# rpi_industrial_hat.net
KiCad netlist of a schematic drawn in EAGLE
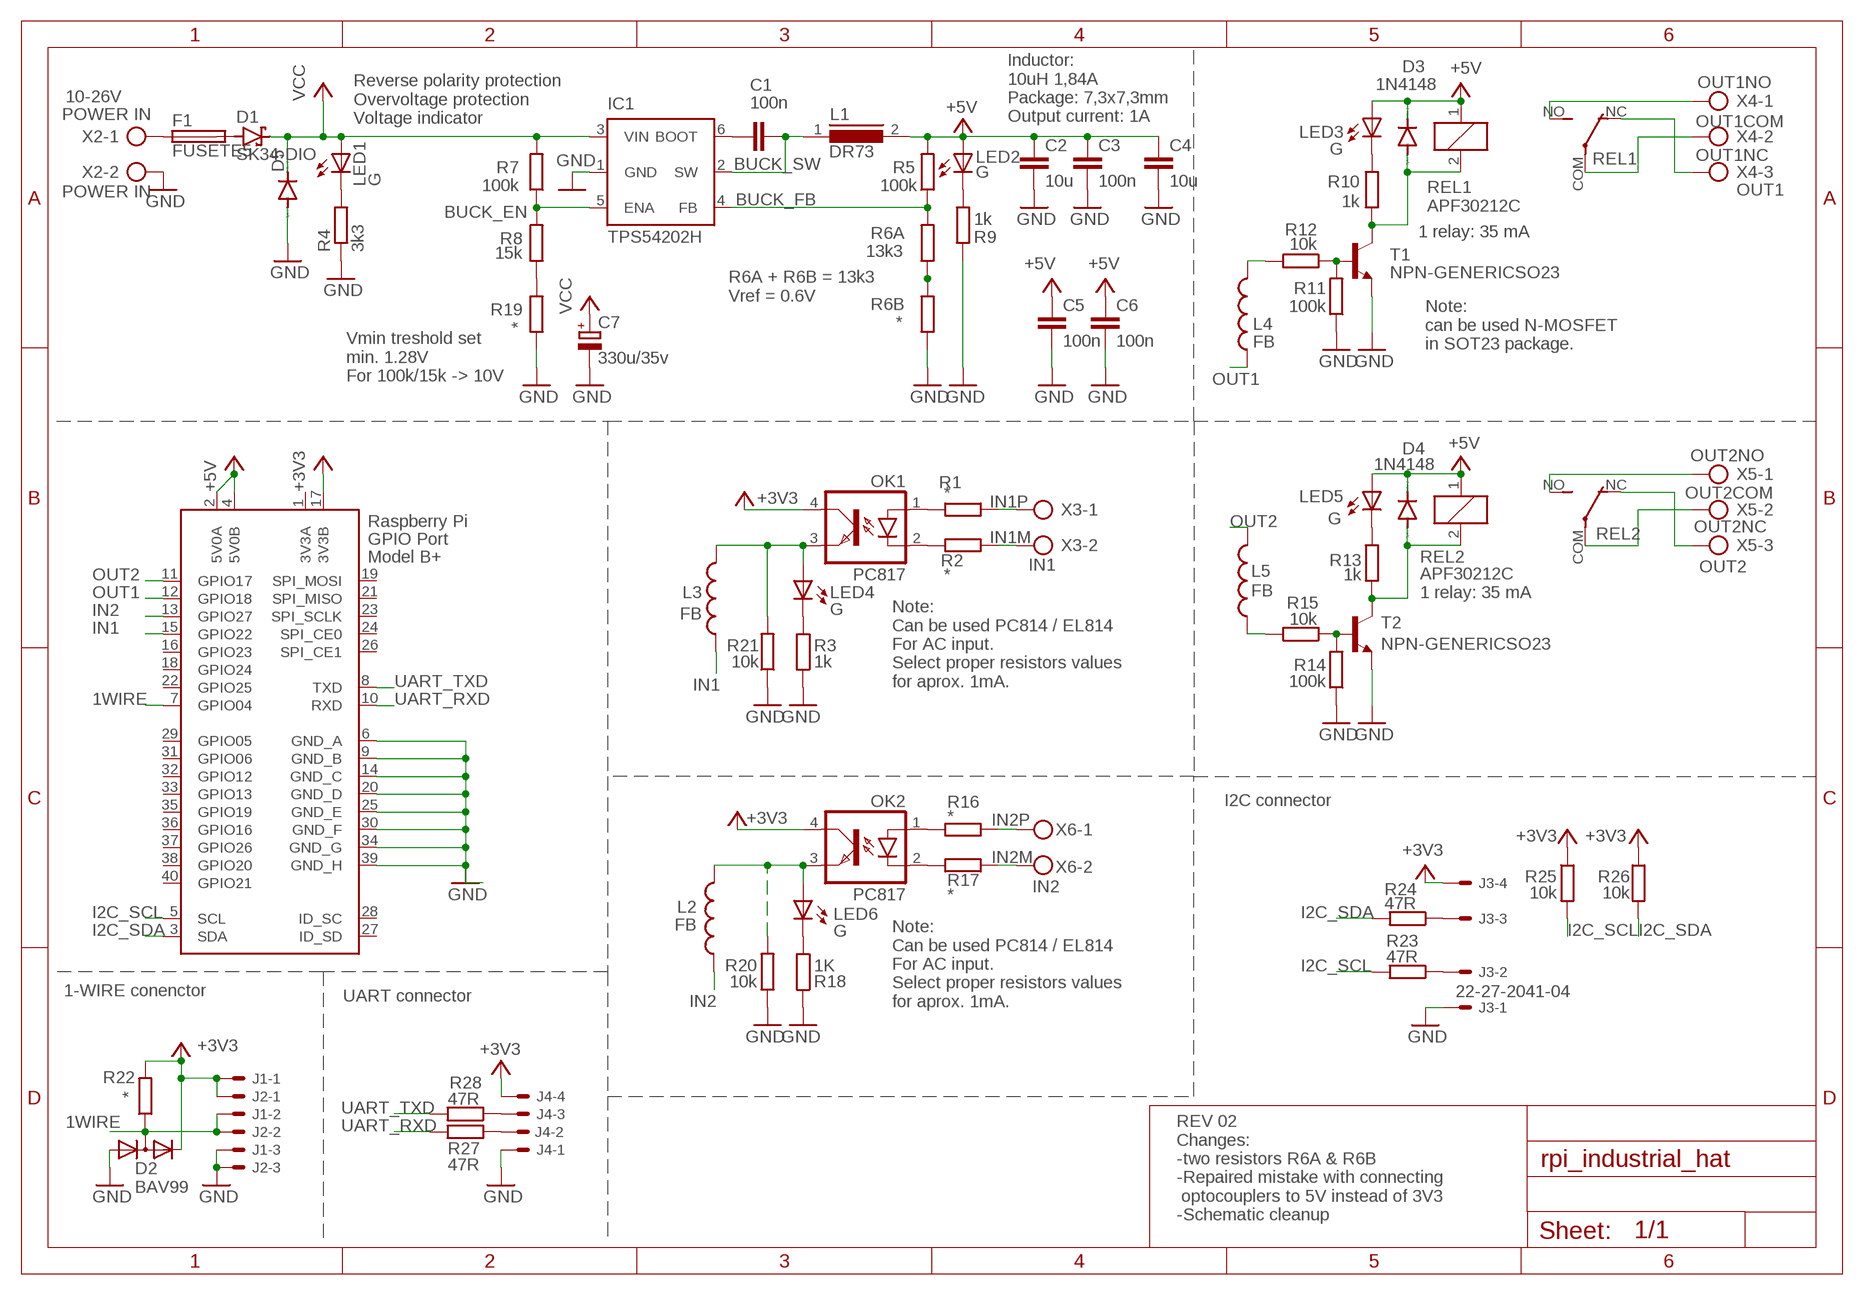
[diagram p0: schematic, sheet 1]

(export (version "E")
  (design (tool "Eeschema 10.0.6"))
  (components
    (comp (ref "C1")
      (value "100n")
      (footprint "eagle-import:C0603")
      (libsource (lib "eagle-import") (part "C-EUC0603"))
    )
    (comp (ref "C2")
      (value "10u")
      (footprint "eagle-import:C0805")
      (libsource (lib "eagle-import") (part "C-EUC0805"))
    )
    (comp (ref "C3")
      (value "100n")
      (footprint "eagle-import:C0603")
      (libsource (lib "eagle-import") (part "C-EUC0603"))
    )
    (comp (ref "C4")
      (value "10u")
      (footprint "eagle-import:C0805")
      (libsource (lib "eagle-import") (part "C-EUC0805"))
    )
    (comp (ref "C5")
      (value "100n")
      (footprint "eagle-import:C0603")
      (libsource (lib "eagle-import") (part "C-EUC0603"))
    )
    (comp (ref "C6")
      (value "100n")
      (footprint "eagle-import:C0603")
      (libsource (lib "eagle-import") (part "C-EUC0603"))
    )
    (comp (ref "C7")
      (value "330u/35v")
      (footprint "eagle-import:E5-10,5")
      (libsource (lib "eagle-import") (part "CPOL-EUE5-10.5"))
    )
    (comp (ref "D1")
      (value "SK34-DIO")
      (footprint "eagle-import:SMC")
      (libsource (lib "eagle-import") (part "SCHOTTKY-DIODESMC"))
    )
    (comp (ref "D2")
      (value "BAV99")
      (footprint "eagle-import:SOT23")
      (libsource (lib "eagle-import") (part "BAV99"))
    )
    (comp (ref "D3")
      (value "1N4148")
      (footprint "eagle-import:MINIMELF")
      (libsource (lib "eagle-import") (part "DIODE-MINIMELF"))
    )
    (comp (ref "D4")
      (value "1N4148")
      (footprint "eagle-import:MINIMELF")
      (libsource (lib "eagle-import") (part "DIODE-MINIMELF"))
    )
    (comp (ref "D5")
      (value "DIODE-DO214AA")
      (footprint "eagle-import:DO214AA")
      (libsource (lib "eagle-import") (part "DIODE-DO214AA"))
    )
    (comp (ref "F1")
      (value "FUSETE5")
      (footprint "eagle-import:TE5")
      (libsource (lib "eagle-import") (part "FUSETE5"))
    )
    (comp (ref "IC1")
      (value "TPS54202H")
      (footprint "eagle-import:SOT23-6")
      (libsource (lib "eagle-import") (part "TPS54202H"))
    )
    (comp (ref "J1")
      (value "22-27-2031-03")
      (footprint "eagle-import:6410-03")
      (fields (field (name "MF") "MOLEX"))
      (libsource (lib "eagle-import") (part "22-?-0327-2031"))
    )
    (comp (ref "J2")
      (value "22-27-2031-03")
      (footprint "eagle-import:6410-03")
      (fields (field (name "MF") "MOLEX"))
      (libsource (lib "eagle-import") (part "22-?-0327-2031"))
    )
    (comp (ref "J3")
      (value "22-27-2041-04")
      (footprint "eagle-import:6410-04")
      (fields (field (name "MF") "MOLEX"))
      (libsource (lib "eagle-import") (part "22-?-0427-2041"))
    )
    (comp (ref "J4")
      (value "22-27-2041-04")
      (footprint "eagle-import:6410-04")
      (fields (field (name "MF") "MOLEX"))
      (libsource (lib "eagle-import") (part "22-?-0427-2041"))
    )
    (comp (ref "L1")
      (value "DR73")
      (footprint "eagle-import:DR73")
      (libsource (lib "eagle-import") (part "DR73"))
    )
    (comp (ref "L2")
      (value "FB")
      (footprint "eagle-import:0603")
      (libsource (lib "eagle-import") (part "INDUCTOR0603"))
    )
    (comp (ref "L3")
      (value "FB")
      (footprint "eagle-import:0603")
      (libsource (lib "eagle-import") (part "INDUCTOR0603"))
    )
    (comp (ref "L4")
      (value "FB")
      (footprint "eagle-import:0603")
      (libsource (lib "eagle-import") (part "INDUCTOR0603"))
    )
    (comp (ref "L5")
      (value "FB")
      (footprint "eagle-import:0603")
      (libsource (lib "eagle-import") (part "INDUCTOR0603"))
    )
    (comp (ref "LED1")
      (value "G")
      (footprint "eagle-import:CHIP-LED0603")
      (libsource (lib "eagle-import") (part "LEDCHIP-LED0603"))
    )
    (comp (ref "LED2")
      (value "G")
      (footprint "eagle-import:CHIP-LED0603")
      (libsource (lib "eagle-import") (part "LEDCHIP-LED0603"))
    )
    (comp (ref "LED3")
      (value "G")
      (footprint "eagle-import:CHIP-LED0603")
      (libsource (lib "eagle-import") (part "LEDCHIP-LED0603"))
    )
    (comp (ref "LED4")
      (value "G")
      (footprint "eagle-import:CHIP-LED0603")
      (libsource (lib "eagle-import") (part "LEDCHIP-LED0603"))
    )
    (comp (ref "LED5")
      (value "G")
      (footprint "eagle-import:CHIP-LED0603")
      (libsource (lib "eagle-import") (part "LEDCHIP-LED0603"))
    )
    (comp (ref "LED6")
      (value "G")
      (footprint "eagle-import:CHIP-LED0603")
      (libsource (lib "eagle-import") (part "LEDCHIP-LED0603"))
    )
    (comp (ref "OK1")
      (value "PC817")
      (footprint "eagle-import:DIL04")
      (fields (field (name "MPN") "PC817X4J000F"))
      (libsource (lib "eagle-import") (part "PC817"))
    )
    (comp (ref "OK2")
      (value "PC817")
      (footprint "eagle-import:DIL04")
      (fields (field (name "MPN") "PC817X4J000F"))
      (libsource (lib "eagle-import") (part "PC817"))
    )
    (comp (ref "R1")
      (value "*")
      (footprint "eagle-import:0204_7_SMD")
      (libsource (lib "eagle-import") (part "R_PROTO_0204/7_0805"))
    )
    (comp (ref "R2")
      (value "*")
      (footprint "eagle-import:0204_7_SMD")
      (libsource (lib "eagle-import") (part "R_PROTO_0204/7_0805"))
    )
    (comp (ref "R3")
      (value "1k")
      (footprint "eagle-import:R0603")
      (libsource (lib "eagle-import") (part "R-EU_R0603"))
    )
    (comp (ref "R4")
      (value "3k3")
      (footprint "eagle-import:R0603")
      (libsource (lib "eagle-import") (part "R-EU_R0603"))
    )
    (comp (ref "R5")
      (value "100k")
      (footprint "eagle-import:R0603")
      (libsource (lib "eagle-import") (part "R-EU_R0603"))
    )
    (comp (ref "R6A")
      (value "13k3")
      (footprint "eagle-import:R0603")
      (libsource (lib "eagle-import") (part "R-EU_R0603"))
    )
    (comp (ref "R6B")
      (value "*")
      (footprint "eagle-import:R0603")
      (libsource (lib "eagle-import") (part "R-EU_R0603"))
    )
    (comp (ref "R7")
      (value "100k")
      (footprint "eagle-import:R0603")
      (libsource (lib "eagle-import") (part "R-EU_R0603"))
    )
    (comp (ref "R8")
      (value "15k")
      (footprint "eagle-import:R0603")
      (libsource (lib "eagle-import") (part "R-EU_R0603"))
    )
    (comp (ref "R9")
      (value "1k")
      (footprint "eagle-import:R0603")
      (libsource (lib "eagle-import") (part "R-EU_R0603"))
    )
    (comp (ref "R10")
      (value "1k")
      (footprint "eagle-import:R0603")
      (libsource (lib "eagle-import") (part "R-EU_R0603"))
    )
    (comp (ref "R11")
      (value "100k")
      (footprint "eagle-import:R0603")
      (libsource (lib "eagle-import") (part "R-EU_R0603"))
    )
    (comp (ref "R12")
      (value "10k")
      (footprint "eagle-import:R0603")
      (libsource (lib "eagle-import") (part "R-EU_R0603"))
    )
    (comp (ref "R13")
      (value "1k")
      (footprint "eagle-import:R0603")
      (libsource (lib "eagle-import") (part "R-EU_R0603"))
    )
    (comp (ref "R14")
      (value "100k")
      (footprint "eagle-import:R0603")
      (libsource (lib "eagle-import") (part "R-EU_R0603"))
    )
    (comp (ref "R15")
      (value "10k")
      (footprint "eagle-import:R0603")
      (libsource (lib "eagle-import") (part "R-EU_R0603"))
    )
    (comp (ref "R16")
      (value "*")
      (footprint "eagle-import:0204_7_SMD")
      (libsource (lib "eagle-import") (part "R_PROTO_0204/7_0805"))
    )
    (comp (ref "R17")
      (value "*")
      (footprint "eagle-import:0204_7_SMD")
      (libsource (lib "eagle-import") (part "R_PROTO_0204/7_0805"))
    )
    (comp (ref "R18")
      (value "1K")
      (footprint "eagle-import:R0603")
      (libsource (lib "eagle-import") (part "R-EU_R0603"))
    )
    (comp (ref "R19")
      (value "*")
      (footprint "eagle-import:R0603")
      (libsource (lib "eagle-import") (part "R-EU_R0603"))
    )
    (comp (ref "R20")
      (value "10k")
      (footprint "eagle-import:R0603")
      (libsource (lib "eagle-import") (part "R-EU_R0603"))
    )
    (comp (ref "R21")
      (value "10k")
      (footprint "eagle-import:R0603")
      (libsource (lib "eagle-import") (part "R-EU_R0603"))
    )
    (comp (ref "R22")
      (value "*")
      (footprint "eagle-import:R0603")
      (libsource (lib "eagle-import") (part "R-EU_R0603"))
    )
    (comp (ref "R23")
      (value "47R")
      (footprint "eagle-import:R0603")
      (libsource (lib "eagle-import") (part "R-EU_R0603"))
    )
    (comp (ref "R24")
      (value "47R")
      (footprint "eagle-import:R0603")
      (libsource (lib "eagle-import") (part "R-EU_R0603"))
    )
    (comp (ref "R25")
      (value "10k")
      (footprint "eagle-import:R0603")
      (libsource (lib "eagle-import") (part "R-EU_R0603"))
    )
    (comp (ref "R26")
      (value "10k")
      (footprint "eagle-import:R0603")
      (libsource (lib "eagle-import") (part "R-EU_R0603"))
    )
    (comp (ref "R27")
      (value "47R")
      (footprint "eagle-import:R0603")
      (libsource (lib "eagle-import") (part "R-EU_R0603"))
    )
    (comp (ref "R28")
      (value "47R")
      (footprint "eagle-import:R0603")
      (libsource (lib "eagle-import") (part "R-EU_R0603"))
    )
    (comp (ref "REL1")
      (value "APF30212C")
      (footprint "eagle-import:APF30212C")
      (libsource (lib "eagle-import") (part "APF30212C"))
    )
    (comp (ref "REL2")
      (value "APF30212C")
      (footprint "eagle-import:APF30212C")
      (libsource (lib "eagle-import") (part "APF30212C"))
    )
    (comp (ref "T1")
      (value "NPN-GENERICSO23")
      (footprint "eagle-import:SOT23")
      (libsource (lib "eagle-import") (part "NPN-GENERICSO23"))
    )
    (comp (ref "T2")
      (value "NPN-GENERICSO23")
      (footprint "eagle-import:SOT23")
      (libsource (lib "eagle-import") (part "NPN-GENERICSO23"))
    )
    (comp (ref "X1")
      (value "RASPI_BOARD_B+#_E4P")
      (footprint "eagle-import:RASPI_BOARD_B+_EDGES_4DRILL_PAD")
      (libsource (lib "eagle-import") (part "RASPI_BOARD_B+#_E4P"))
    )
    (comp (ref "X2")
      (value "POWER IN")
      (footprint "eagle-import:AK500_2")
      (libsource (lib "eagle-import") (part "AK500/2"))
    )
    (comp (ref "X3")
      (value "IN1")
      (footprint "eagle-import:AK500_2")
      (libsource (lib "eagle-import") (part "AK500/2"))
    )
    (comp (ref "X4")
      (value "OUT1")
      (footprint "eagle-import:AK500_3")
      (libsource (lib "eagle-import") (part "AK500/3"))
    )
    (comp (ref "X5")
      (value "OUT2")
      (footprint "eagle-import:AK500_3")
      (libsource (lib "eagle-import") (part "AK500/3"))
    )
    (comp (ref "X6")
      (value "IN2")
      (footprint "eagle-import:AK500_2")
      (libsource (lib "eagle-import") (part "AK500/2"))
    )
  )
  (nets
    (net (code "1") (name "+3V3") (class "Default")
      (node (ref "D2") (pin "2") (pinfunction "K2_2") (pintype "passive"))
      (node (ref "J1") (pin "1") (pinfunction "S_1") (pintype "passive"))
      (node (ref "J2") (pin "1") (pinfunction "S_1") (pintype "passive"))
      (node (ref "J3") (pin "4") (pinfunction "S_4") (pintype "passive"))
      (node (ref "J4") (pin "4") (pinfunction "S_4") (pintype "passive"))
      (node (ref "OK1") (pin "4") (pinfunction "COL_4") (pintype "passive"))
      (node (ref "OK2") (pin "4") (pinfunction "COL_4") (pintype "passive"))
      (node (ref "R22") (pin "2") (pinfunction "2_2") (pintype "passive"))
      (node (ref "R25") (pin "1") (pinfunction "1_1") (pintype "passive"))
      (node (ref "R26") (pin "1") (pinfunction "1_1") (pintype "passive"))
      (node (ref "X1") (pin "17") (pinfunction "3V3B_17") (pintype "power_in"))
    )
    (net (code "2") (name "+5V") (class "Default")
      (node (ref "C2") (pin "1") (pinfunction "1_1") (pintype "passive"))
      (node (ref "C3") (pin "1") (pinfunction "1_1") (pintype "passive"))
      (node (ref "C4") (pin "1") (pinfunction "1_1") (pintype "passive"))
      (node (ref "C5") (pin "1") (pinfunction "1_1") (pintype "passive"))
      (node (ref "C6") (pin "1") (pinfunction "1_1") (pintype "passive"))
      (node (ref "D3") (pin "C") (pinfunction "C_C") (pintype "passive"))
      (node (ref "D4") (pin "C") (pinfunction "C_C") (pintype "passive"))
      (node (ref "L1") (pin "2") (pinfunction "2_2") (pintype "passive"))
      (node (ref "LED2") (pin "A") (pinfunction "A_A") (pintype "passive"))
      (node (ref "LED3") (pin "A") (pinfunction "A_A") (pintype "passive"))
      (node (ref "LED5") (pin "A") (pinfunction "A_A") (pintype "passive"))
      (node (ref "R5") (pin "2") (pinfunction "2_2") (pintype "passive"))
      (node (ref "REL1") (pin "1") (pinfunction "1_1") (pintype "passive"))
      (node (ref "REL2") (pin "1") (pinfunction "1_1") (pintype "passive"))
      (node (ref "X1") (pin "2") (pinfunction "5V0A_2") (pintype "power_in"))
      (node (ref "X1") (pin "4") (pinfunction "5V0B_4") (pintype "power_in"))
    )
    (net (code "3") (name "/1WIRE") (class "Default")
      (node (ref "D2") (pin "3") (pinfunction "K1A2_3") (pintype "passive"))
      (node (ref "J1") (pin "2") (pinfunction "S_2") (pintype "passive"))
      (node (ref "J2") (pin "2") (pinfunction "S_2") (pintype "passive"))
      (node (ref "R22") (pin "1") (pinfunction "1_1") (pintype "passive"))
      (node (ref "X1") (pin "7") (pinfunction "GPIO04_7") (pintype "bidirectional"))
    )
    (net (code "4") (name "/3V3A") (class "Default")
      (node (ref "X1") (pin "1") (pinfunction "3V3A_1") (pintype "power_in"))
    )
    (net (code "5") (name "/BUCK_EN") (class "Default")
      (node (ref "IC1") (pin "5") (pinfunction "ENA_5") (pintype "input"))
      (node (ref "R7") (pin "1") (pinfunction "1_1") (pintype "passive"))
      (node (ref "R8") (pin "2") (pinfunction "2_2") (pintype "passive"))
    )
    (net (code "6") (name "/BUCK_FB") (class "Default")
      (node (ref "IC1") (pin "4") (pinfunction "FB_4") (pintype "input"))
      (node (ref "R5") (pin "1") (pinfunction "1_1") (pintype "passive"))
      (node (ref "R6A") (pin "2") (pinfunction "2_2") (pintype "passive"))
    )
    (net (code "7") (name "/BUCK_SW") (class "Default")
      (node (ref "C1") (pin "2") (pinfunction "2_2") (pintype "passive"))
      (node (ref "IC1") (pin "2") (pinfunction "SW_2") (pintype "output"))
      (node (ref "L1") (pin "1") (pinfunction "1_1") (pintype "passive"))
    )
    (net (code "8") (name "/I2C_SCL") (class "Default")
      (node (ref "R23") (pin "2") (pinfunction "2_2") (pintype "passive"))
      (node (ref "R25") (pin "2") (pinfunction "2_2") (pintype "passive"))
      (node (ref "X1") (pin "5") (pinfunction "SCL_5") (pintype "bidirectional"))
    )
    (net (code "9") (name "/I2C_SDA") (class "Default")
      (node (ref "R24") (pin "2") (pinfunction "2_2") (pintype "passive"))
      (node (ref "R26") (pin "2") (pinfunction "2_2") (pintype "passive"))
      (node (ref "X1") (pin "3") (pinfunction "SDA_3") (pintype "bidirectional"))
    )
    (net (code "10") (name "/IN1") (class "Default")
      (node (ref "L3") (pin "1") (pinfunction "1_1") (pintype "passive"))
      (node (ref "X1") (pin "15") (pinfunction "GPIO22_15") (pintype "bidirectional"))
    )
    (net (code "11") (name "/IN1M") (class "Default")
      (node (ref "R2") (pin "1") (pinfunction "1_1") (pintype "passive"))
      (node (ref "X3") (pin "2") (pinfunction "KL_2") (pintype "passive"))
    )
    (net (code "12") (name "/IN1P") (class "Default")
      (node (ref "R1") (pin "1") (pinfunction "1_1") (pintype "passive"))
      (node (ref "X3") (pin "1") (pinfunction "KL_1") (pintype "passive"))
    )
    (net (code "13") (name "/IN2") (class "Default")
      (node (ref "L2") (pin "1") (pinfunction "1_1") (pintype "passive"))
      (node (ref "X1") (pin "13") (pinfunction "GPIO27_13") (pintype "bidirectional"))
    )
    (net (code "14") (name "/IN2M") (class "Default")
      (node (ref "R17") (pin "1") (pinfunction "1_1") (pintype "passive"))
      (node (ref "X6") (pin "2") (pinfunction "KL_2") (pintype "passive"))
    )
    (net (code "15") (name "/IN2P") (class "Default")
      (node (ref "R16") (pin "1") (pinfunction "1_1") (pintype "passive"))
      (node (ref "X6") (pin "1") (pinfunction "KL_1") (pintype "passive"))
    )
    (net (code "16") (name "/OUT1") (class "Default")
      (node (ref "L4") (pin "1") (pinfunction "1_1") (pintype "passive"))
      (node (ref "X1") (pin "12") (pinfunction "GPIO18_12") (pintype "bidirectional"))
    )
    (net (code "17") (name "/OUT1COM") (class "Default")
      (node (ref "REL1") (pin "COM") (pinfunction "P_COM") (pintype "passive"))
      (node (ref "X4") (pin "2") (pinfunction "KL_2") (pintype "passive"))
    )
    (net (code "18") (name "/OUT1NC") (class "Default")
      (node (ref "REL1") (pin "NC") (pinfunction "O_NC") (pintype "passive"))
      (node (ref "X4") (pin "3") (pinfunction "KL_3") (pintype "passive"))
    )
    (net (code "19") (name "/OUT1NO") (class "Default")
      (node (ref "REL1") (pin "NO") (pinfunction "S_NO") (pintype "passive"))
      (node (ref "X4") (pin "1") (pinfunction "KL_1") (pintype "passive"))
    )
    (net (code "20") (name "/OUT2") (class "Default")
      (node (ref "L5") (pin "2") (pinfunction "2_2") (pintype "passive"))
      (node (ref "X1") (pin "11") (pinfunction "GPIO17_11") (pintype "bidirectional"))
    )
    (net (code "21") (name "/OUT2COM") (class "Default")
      (node (ref "REL2") (pin "COM") (pinfunction "P_COM") (pintype "passive"))
      (node (ref "X5") (pin "2") (pinfunction "KL_2") (pintype "passive"))
    )
    (net (code "22") (name "/OUT2NC") (class "Default")
      (node (ref "REL2") (pin "NC") (pinfunction "O_NC") (pintype "passive"))
      (node (ref "X5") (pin "3") (pinfunction "KL_3") (pintype "passive"))
    )
    (net (code "23") (name "/OUT2NO") (class "Default")
      (node (ref "REL2") (pin "NO") (pinfunction "S_NO") (pintype "passive"))
      (node (ref "X5") (pin "1") (pinfunction "KL_1") (pintype "passive"))
    )
    (net (code "24") (name "/UART_RXD") (class "Default")
      (node (ref "R27") (pin "2") (pinfunction "2_2") (pintype "passive"))
      (node (ref "X1") (pin "10") (pinfunction "RXD_10") (pintype "bidirectional"))
    )
    (net (code "25") (name "/UART_TXD") (class "Default")
      (node (ref "R28") (pin "2") (pinfunction "2_2") (pintype "passive"))
      (node (ref "X1") (pin "8") (pinfunction "TXD_8") (pintype "bidirectional"))
    )
    (net (code "26") (name "GND") (class "Default")
      (node (ref "C2") (pin "2") (pinfunction "2_2") (pintype "passive"))
      (node (ref "C3") (pin "2") (pinfunction "2_2") (pintype "passive"))
      (node (ref "C4") (pin "2") (pinfunction "2_2") (pintype "passive"))
      (node (ref "C5") (pin "2") (pinfunction "2_2") (pintype "passive"))
      (node (ref "C6") (pin "2") (pinfunction "2_2") (pintype "passive"))
      (node (ref "C7") (pin "-") (pinfunction "-_-") (pintype "passive"))
      (node (ref "D2") (pin "1") (pinfunction "A1_1") (pintype "passive"))
      (node (ref "D5") (pin "A") (pinfunction "A_A") (pintype "passive"))
      (node (ref "IC1") (pin "1") (pinfunction "GND_1") (pintype "power_in"))
      (node (ref "J1") (pin "3") (pinfunction "S_3") (pintype "passive"))
      (node (ref "J2") (pin "3") (pinfunction "S_3") (pintype "passive"))
      (node (ref "J3") (pin "1") (pinfunction "S_1") (pintype "passive"))
      (node (ref "J4") (pin "1") (pinfunction "S_1") (pintype "passive"))
      (node (ref "R11") (pin "1") (pinfunction "1_1") (pintype "passive"))
      (node (ref "R14") (pin "1") (pinfunction "1_1") (pintype "passive"))
      (node (ref "R18") (pin "1") (pinfunction "1_1") (pintype "passive"))
      (node (ref "R19") (pin "1") (pinfunction "1_1") (pintype "passive"))
      (node (ref "R20") (pin "1") (pinfunction "1_1") (pintype "passive"))
      (node (ref "R21") (pin "1") (pinfunction "1_1") (pintype "passive"))
      (node (ref "R3") (pin "1") (pinfunction "1_1") (pintype "passive"))
      (node (ref "R4") (pin "1") (pinfunction "1_1") (pintype "passive"))
      (node (ref "R6B") (pin "1") (pinfunction "1_1") (pintype "passive"))
      (node (ref "R9") (pin "1") (pinfunction "1_1") (pintype "passive"))
      (node (ref "T1") (pin "2") (pinfunction "E_2") (pintype "passive"))
      (node (ref "T2") (pin "2") (pinfunction "E_2") (pintype "passive"))
      (node (ref "X1") (pin "14") (pinfunction "GND_C_14") (pintype "power_in"))
      (node (ref "X1") (pin "20") (pinfunction "GND_D_20") (pintype "power_in"))
      (node (ref "X1") (pin "25") (pinfunction "GND_E_25") (pintype "power_in"))
      (node (ref "X1") (pin "30") (pinfunction "GND_F_30") (pintype "power_in"))
      (node (ref "X1") (pin "34") (pinfunction "GND_G_34") (pintype "power_in"))
      (node (ref "X1") (pin "39") (pinfunction "GND_H_39") (pintype "power_in"))
      (node (ref "X1") (pin "6") (pinfunction "GND_A_6") (pintype "power_in"))
      (node (ref "X1") (pin "9") (pinfunction "GND_B_9") (pintype "power_in"))
      (node (ref "X2") (pin "2") (pinfunction "KL_2") (pintype "passive"))
    )
    (net (code "27") (name "Net-(D1-PadA)") (class "Default")
      (node (ref "D1") (pin "A") (pinfunction "A_A") (pintype "passive"))
      (node (ref "F1") (pin "2") (pinfunction "2_2") (pintype "passive"))
    )
    (net (code "28") (name "Net-(IC1-BOOT)") (class "Default")
      (node (ref "C1") (pin "1") (pinfunction "1_1") (pintype "passive"))
      (node (ref "IC1") (pin "6") (pinfunction "BOOT_6") (pintype "output"))
    )
    (net (code "29") (name "Net-(J3B-S)") (class "Default")
      (node (ref "J3") (pin "2") (pinfunction "S_2") (pintype "passive"))
      (node (ref "R23") (pin "1") (pinfunction "1_1") (pintype "passive"))
    )
    (net (code "30") (name "Net-(J3C-S)") (class "Default")
      (node (ref "J3") (pin "3") (pinfunction "S_3") (pintype "passive"))
      (node (ref "R24") (pin "1") (pinfunction "1_1") (pintype "passive"))
    )
    (net (code "31") (name "Net-(J4B-S)") (class "Default")
      (node (ref "J4") (pin "2") (pinfunction "S_2") (pintype "passive"))
      (node (ref "R27") (pin "1") (pinfunction "1_1") (pintype "passive"))
    )
    (net (code "32") (name "Net-(J4C-S)") (class "Default")
      (node (ref "J4") (pin "3") (pinfunction "S_3") (pintype "passive"))
      (node (ref "R28") (pin "1") (pinfunction "1_1") (pintype "passive"))
    )
    (net (code "33") (name "Net-(L4-Pad2)") (class "Default")
      (node (ref "L4") (pin "2") (pinfunction "2_2") (pintype "passive"))
      (node (ref "R12") (pin "2") (pinfunction "2_2") (pintype "passive"))
    )
    (net (code "34") (name "Net-(L5-Pad1)") (class "Default")
      (node (ref "L5") (pin "1") (pinfunction "1_1") (pintype "passive"))
      (node (ref "R15") (pin "2") (pinfunction "2_2") (pintype "passive"))
    )
    (net (code "35") (name "Net-(LED1-PadC)") (class "Default")
      (node (ref "LED1") (pin "C") (pinfunction "C_C") (pintype "passive"))
      (node (ref "R4") (pin "2") (pinfunction "2_2") (pintype "passive"))
    )
    (net (code "36") (name "Net-(LED2-PadC)") (class "Default")
      (node (ref "LED2") (pin "C") (pinfunction "C_C") (pintype "passive"))
      (node (ref "R9") (pin "2") (pinfunction "2_2") (pintype "passive"))
    )
    (net (code "37") (name "Net-(LED3-PadC)") (class "Default")
      (node (ref "LED3") (pin "C") (pinfunction "C_C") (pintype "passive"))
      (node (ref "R10") (pin "2") (pinfunction "2_2") (pintype "passive"))
    )
    (net (code "38") (name "Net-(LED4-PadC)") (class "Default")
      (node (ref "LED4") (pin "C") (pinfunction "C_C") (pintype "passive"))
      (node (ref "R3") (pin "2") (pinfunction "2_2") (pintype "passive"))
    )
    (net (code "39") (name "Net-(LED5-PadC)") (class "Default")
      (node (ref "LED5") (pin "C") (pinfunction "C_C") (pintype "passive"))
      (node (ref "R13") (pin "2") (pinfunction "2_2") (pintype "passive"))
    )
    (net (code "40") (name "Net-(LED6-PadC)") (class "Default")
      (node (ref "LED6") (pin "C") (pinfunction "C_C") (pintype "passive"))
      (node (ref "R18") (pin "2") (pinfunction "2_2") (pintype "passive"))
    )
    (net (code "41") (name "Net-(OK1-A)") (class "Default")
      (node (ref "OK1") (pin "1") (pinfunction "A_1") (pintype "passive"))
      (node (ref "R1") (pin "2") (pinfunction "2_2") (pintype "passive"))
    )
    (net (code "42") (name "Net-(OK1-C)") (class "Default")
      (node (ref "OK1") (pin "2") (pinfunction "C_2") (pintype "passive"))
      (node (ref "R2") (pin "2") (pinfunction "2_2") (pintype "passive"))
    )
    (net (code "43") (name "Net-(OK1-EMIT)") (class "Default")
      (node (ref "L3") (pin "2") (pinfunction "2_2") (pintype "passive"))
      (node (ref "LED4") (pin "A") (pinfunction "A_A") (pintype "passive"))
      (node (ref "OK1") (pin "3") (pinfunction "EMIT_3") (pintype "passive"))
      (node (ref "R21") (pin "2") (pinfunction "2_2") (pintype "passive"))
    )
    (net (code "44") (name "Net-(OK2-A)") (class "Default")
      (node (ref "OK2") (pin "1") (pinfunction "A_1") (pintype "passive"))
      (node (ref "R16") (pin "2") (pinfunction "2_2") (pintype "passive"))
    )
    (net (code "45") (name "Net-(OK2-C)") (class "Default")
      (node (ref "OK2") (pin "2") (pinfunction "C_2") (pintype "passive"))
      (node (ref "R17") (pin "2") (pinfunction "2_2") (pintype "passive"))
    )
    (net (code "46") (name "Net-(OK2-EMIT)") (class "Default")
      (node (ref "L2") (pin "2") (pinfunction "2_2") (pintype "passive"))
      (node (ref "LED6") (pin "A") (pinfunction "A_A") (pintype "passive"))
      (node (ref "OK2") (pin "3") (pinfunction "EMIT_3") (pintype "passive"))
      (node (ref "R20") (pin "2") (pinfunction "2_2") (pintype "passive"))
    )
    (net (code "47") (name "Net-(R6A-Pad1)") (class "Default")
      (node (ref "R6A") (pin "1") (pinfunction "1_1") (pintype "passive"))
      (node (ref "R6B") (pin "2") (pinfunction "2_2") (pintype "passive"))
    )
    (net (code "48") (name "Net-(R19-Pad2)") (class "Default")
      (node (ref "R19") (pin "2") (pinfunction "2_2") (pintype "passive"))
      (node (ref "R8") (pin "1") (pinfunction "1_1") (pintype "passive"))
    )
    (net (code "49") (name "Net-(T1-B)") (class "Default")
      (node (ref "R11") (pin "2") (pinfunction "2_2") (pintype "passive"))
      (node (ref "R12") (pin "1") (pinfunction "1_1") (pintype "passive"))
      (node (ref "T1") (pin "1") (pinfunction "B_1") (pintype "passive"))
    )
    (net (code "50") (name "Net-(T1-C)") (class "Default")
      (node (ref "D3") (pin "A") (pinfunction "A_A") (pintype "passive"))
      (node (ref "R10") (pin "1") (pinfunction "1_1") (pintype "passive"))
      (node (ref "REL1") (pin "2") (pinfunction "2_2") (pintype "passive"))
      (node (ref "T1") (pin "3") (pinfunction "C_3") (pintype "passive"))
    )
    (net (code "51") (name "Net-(T2-B)") (class "Default")
      (node (ref "R14") (pin "2") (pinfunction "2_2") (pintype "passive"))
      (node (ref "R15") (pin "1") (pinfunction "1_1") (pintype "passive"))
      (node (ref "T2") (pin "1") (pinfunction "B_1") (pintype "passive"))
    )
    (net (code "52") (name "Net-(T2-C)") (class "Default")
      (node (ref "D4") (pin "A") (pinfunction "A_A") (pintype "passive"))
      (node (ref "R13") (pin "1") (pinfunction "1_1") (pintype "passive"))
      (node (ref "REL2") (pin "2") (pinfunction "2_2") (pintype "passive"))
      (node (ref "T2") (pin "3") (pinfunction "C_3") (pintype "passive"))
    )
    (net (code "53") (name "Net-(X2A-KL)") (class "Default")
      (node (ref "F1") (pin "1") (pinfunction "1_1") (pintype "passive"))
      (node (ref "X2") (pin "1") (pinfunction "KL_1") (pintype "passive"))
    )
    (net (code "54") (name "VCC") (class "Default")
      (node (ref "C7") (pin "+") (pinfunction "+_+") (pintype "passive"))
      (node (ref "D1") (pin "C") (pinfunction "C_C") (pintype "passive"))
      (node (ref "D5") (pin "C") (pinfunction "C_C") (pintype "passive"))
      (node (ref "IC1") (pin "3") (pinfunction "VIN_3") (pintype "power_in"))
      (node (ref "LED1") (pin "A") (pinfunction "A_A") (pintype "passive"))
      (node (ref "R7") (pin "2") (pinfunction "2_2") (pintype "passive"))
    )
    (net (code "55") (name "unconnected-(X1-GPIO05-Pad29)") (class "Default")
      (node (ref "X1") (pin "29") (pinfunction "GPIO05_29") (pintype "no_connect"))
    )
    (net (code "56") (name "unconnected-(X1-GPIO06-Pad31)") (class "Default")
      (node (ref "X1") (pin "31") (pinfunction "GPIO06_31") (pintype "no_connect"))
    )
    (net (code "57") (name "unconnected-(X1-GPIO12-Pad32)") (class "Default")
      (node (ref "X1") (pin "32") (pinfunction "GPIO12_32") (pintype "no_connect"))
    )
    (net (code "58") (name "unconnected-(X1-GPIO13-Pad33)") (class "Default")
      (node (ref "X1") (pin "33") (pinfunction "GPIO13_33") (pintype "no_connect"))
    )
    (net (code "59") (name "unconnected-(X1-GPIO16-Pad36)") (class "Default")
      (node (ref "X1") (pin "36") (pinfunction "GPIO16_36") (pintype "no_connect"))
    )
    (net (code "60") (name "unconnected-(X1-GPIO19-Pad35)") (class "Default")
      (node (ref "X1") (pin "35") (pinfunction "GPIO19_35") (pintype "no_connect"))
    )
    (net (code "61") (name "unconnected-(X1-GPIO20-Pad38)") (class "Default")
      (node (ref "X1") (pin "38") (pinfunction "GPIO20_38") (pintype "no_connect"))
    )
    (net (code "62") (name "unconnected-(X1-GPIO21-Pad40)") (class "Default")
      (node (ref "X1") (pin "40") (pinfunction "GPIO21_40") (pintype "no_connect"))
    )
    (net (code "63") (name "unconnected-(X1-GPIO23-Pad16)") (class "Default")
      (node (ref "X1") (pin "16") (pinfunction "GPIO23_16") (pintype "bidirectional"))
    )
    (net (code "64") (name "unconnected-(X1-GPIO24-Pad18)") (class "Default")
      (node (ref "X1") (pin "18") (pinfunction "GPIO24_18") (pintype "bidirectional"))
    )
    (net (code "65") (name "unconnected-(X1-GPIO25-Pad22)") (class "Default")
      (node (ref "X1") (pin "22") (pinfunction "GPIO25_22") (pintype "bidirectional"))
    )
    (net (code "66") (name "unconnected-(X1-GPIO26-Pad37)") (class "Default")
      (node (ref "X1") (pin "37") (pinfunction "GPIO26_37") (pintype "no_connect"))
    )
    (net (code "67") (name "unconnected-(X1-ID_SC-Pad28)") (class "Default")
      (node (ref "X1") (pin "28") (pinfunction "ID_SC_28") (pintype "no_connect"))
    )
    (net (code "68") (name "unconnected-(X1-ID_SD-Pad27)") (class "Default")
      (node (ref "X1") (pin "27") (pinfunction "ID_SD_27") (pintype "no_connect"))
    )
    (net (code "69") (name "unconnected-(X1-SPI_CE0-Pad24)") (class "Default")
      (node (ref "X1") (pin "24") (pinfunction "SPI_CE0_24") (pintype "bidirectional"))
    )
    (net (code "70") (name "unconnected-(X1-SPI_CE1-Pad26)") (class "Default")
      (node (ref "X1") (pin "26") (pinfunction "SPI_CE1_26") (pintype "bidirectional"))
    )
    (net (code "71") (name "unconnected-(X1-SPI_MISO-Pad21)") (class "Default")
      (node (ref "X1") (pin "21") (pinfunction "SPI_MISO_21") (pintype "bidirectional"))
    )
    (net (code "72") (name "unconnected-(X1-SPI_MOSI-Pad19)") (class "Default")
      (node (ref "X1") (pin "19") (pinfunction "SPI_MOSI_19") (pintype "bidirectional"))
    )
    (net (code "73") (name "unconnected-(X1-SPI_SCLK-Pad23)") (class "Default")
      (node (ref "X1") (pin "23") (pinfunction "SPI_SCLK_23") (pintype "bidirectional"))
    )
  )
)
